# pneumaticsBoard.net
KiCad netlist of a schematic drawn in EAGLE
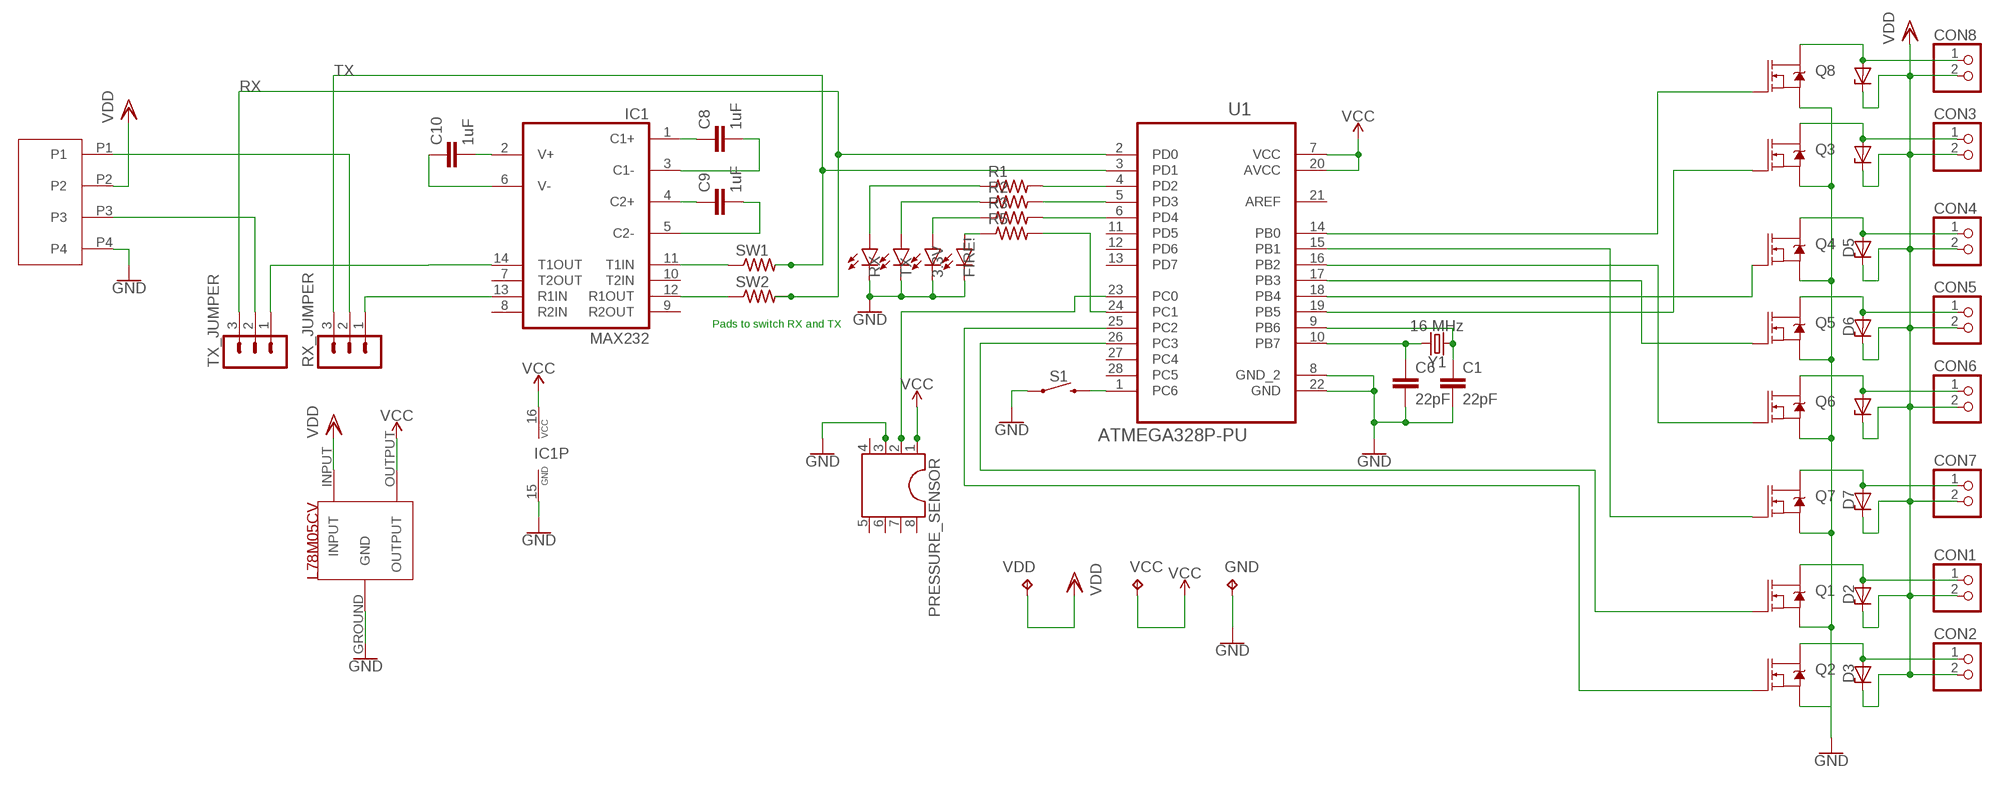
[diagram p0: schematic, sheet 1]

(export (version "E")
  (design (tool "Eeschema 10.0.6"))
  (components
    (comp (ref "3.3V")
      (value "BLUE")
      (footprint "eagle-import:LED-0603")
      (libsource (lib "eagle-import") (part "LED-BLUE0603"))
    )
    (comp (ref "C1")
      (value "22pF")
      (footprint "eagle-import:0603")
      (libsource (lib "eagle-import") (part "470PF-0603-50V-5%"))
    )
    (comp (ref "C6")
      (value "22pF")
      (footprint "eagle-import:0603")
      (libsource (lib "eagle-import") (part "470PF-0603-50V-5%"))
    )
    (comp (ref "C8")
      (value "1uF")
      (footprint "eagle-import:0603")
      (libsource (lib "eagle-import") (part "470PF-0603-50V-5%"))
    )
    (comp (ref "C9")
      (value "1uF")
      (footprint "eagle-import:0603")
      (libsource (lib "eagle-import") (part "470PF-0603-50V-5%"))
    )
    (comp (ref "C10")
      (value "1uF")
      (footprint "eagle-import:0603")
      (libsource (lib "eagle-import") (part "470PF-0603-50V-5%"))
    )
    (comp (ref "CON1")
      (value "PINHD-1X2")
      (footprint "eagle-import:1X02")
      (libsource (lib "eagle-import") (part "PINHD-1X2"))
    )
    (comp (ref "CON2")
      (value "PINHD-1X2")
      (footprint "eagle-import:1X02")
      (libsource (lib "eagle-import") (part "PINHD-1X2"))
    )
    (comp (ref "CON3")
      (value "PINHD-1X2")
      (footprint "eagle-import:1X02")
      (libsource (lib "eagle-import") (part "PINHD-1X2"))
    )
    (comp (ref "CON4")
      (value "PINHD-1X2")
      (footprint "eagle-import:1X02")
      (libsource (lib "eagle-import") (part "PINHD-1X2"))
    )
    (comp (ref "CON5")
      (value "PINHD-1X2")
      (footprint "eagle-import:1X02")
      (libsource (lib "eagle-import") (part "PINHD-1X2"))
    )
    (comp (ref "CON6")
      (value "PINHD-1X2")
      (footprint "eagle-import:1X02")
      (libsource (lib "eagle-import") (part "PINHD-1X2"))
    )
    (comp (ref "CON7")
      (value "PINHD-1X2")
      (footprint "eagle-import:1X02")
      (libsource (lib "eagle-import") (part "PINHD-1X2"))
    )
    (comp (ref "CON8")
      (value "PINHD-1X2")
      (footprint "eagle-import:1X02")
      (libsource (lib "eagle-import") (part "PINHD-1X2"))
    )
    (comp (ref "D1")
      (value "BZX90")
      (footprint "eagle-import:DO34Z7")
      (libsource (lib "eagle-import") (part "BZX90"))
    )
    (comp (ref "D2")
      (value "BZX90")
      (footprint "eagle-import:DO34Z7")
      (libsource (lib "eagle-import") (part "BZX90"))
    )
    (comp (ref "D3")
      (value "BZX90")
      (footprint "eagle-import:DO34Z7")
      (libsource (lib "eagle-import") (part "BZX90"))
    )
    (comp (ref "D4")
      (value "BZX90")
      (footprint "eagle-import:DO34Z7")
      (libsource (lib "eagle-import") (part "BZX90"))
    )
    (comp (ref "D5")
      (value "BZX90")
      (footprint "eagle-import:DO34Z7")
      (libsource (lib "eagle-import") (part "BZX90"))
    )
    (comp (ref "D6")
      (value "BZX90")
      (footprint "eagle-import:DO34Z7")
      (libsource (lib "eagle-import") (part "BZX90"))
    )
    (comp (ref "D7")
      (value "BZX90")
      (footprint "eagle-import:DO34Z7")
      (libsource (lib "eagle-import") (part "BZX90"))
    )
    (comp (ref "D8")
      (value "BZX90")
      (footprint "eagle-import:DO34Z7")
      (libsource (lib "eagle-import") (part "BZX90"))
    )
    (comp (ref "FIRE!")
      (value "BLUE")
      (footprint "eagle-import:LED-0603")
      (libsource (lib "eagle-import") (part "LED-BLUE0603"))
    )
    (comp (ref "GND")
      (value "TPTP11R")
      (footprint "eagle-import:TP11R")
      (libsource (lib "eagle-import") (part "TPTP11R"))
    )
    (comp (ref "IC1")
      (value "MAX232")
      (footprint "eagle-import:DIL16")
      (fields (field (name "MF") "MAXIM") (field (name "MPN") "MAX232ACPE+"))
      (libsource (lib "eagle-import") (part "MAX232"))
    )
    (comp (ref "PRESSURE_SENSOR")
      (value "DIL8")
      (footprint "eagle-import:DIL08")
      (libsource (lib "eagle-import") (part "DIL8"))
    )
    (comp (ref "Q1")
      (value "60V/32A/35mΩ")
      (footprint "eagle-import:TO220V")
      (libsource (lib "eagle-import") (part "MOSFET-NCH-FQP30N06L"))
    )
    (comp (ref "Q2")
      (value "60V/32A/35mΩ")
      (footprint "eagle-import:TO220V")
      (libsource (lib "eagle-import") (part "MOSFET-NCH-FQP30N06L"))
    )
    (comp (ref "Q3")
      (value "60V/32A/35mΩ")
      (footprint "eagle-import:TO220V")
      (libsource (lib "eagle-import") (part "MOSFET-NCH-FQP30N06L"))
    )
    (comp (ref "Q4")
      (value "60V/32A/35mΩ")
      (footprint "eagle-import:TO220V")
      (libsource (lib "eagle-import") (part "MOSFET-NCH-FQP30N06L"))
    )
    (comp (ref "Q5")
      (value "60V/32A/35mΩ")
      (footprint "eagle-import:TO220V")
      (libsource (lib "eagle-import") (part "MOSFET-NCH-FQP30N06L"))
    )
    (comp (ref "Q6")
      (value "60V/32A/35mΩ")
      (footprint "eagle-import:TO220V")
      (libsource (lib "eagle-import") (part "MOSFET-NCH-FQP30N06L"))
    )
    (comp (ref "Q7")
      (value "60V/32A/35mΩ")
      (footprint "eagle-import:TO220V")
      (libsource (lib "eagle-import") (part "MOSFET-NCH-FQP30N06L"))
    )
    (comp (ref "Q8")
      (value "60V/32A/35mΩ")
      (footprint "eagle-import:TO220V")
      (libsource (lib "eagle-import") (part "MOSFET-NCH-FQP30N06L"))
    )
    (comp (ref "R1")
      (value "R-US_0204/2V")
      (footprint "eagle-import:0204V")
      (libsource (lib "eagle-import") (part "R-US_0204/2V"))
    )
    (comp (ref "R2")
      (value "R-US_0204/2V")
      (footprint "eagle-import:0204V")
      (libsource (lib "eagle-import") (part "R-US_0204/2V"))
    )
    (comp (ref "R3")
      (value "R-US_0204/2V")
      (footprint "eagle-import:0204V")
      (libsource (lib "eagle-import") (part "R-US_0204/2V"))
    )
    (comp (ref "R5")
      (value "R-US_0204/2V")
      (footprint "eagle-import:0204V")
      (libsource (lib "eagle-import") (part "R-US_0204/2V"))
    )
    (comp (ref "RX")
      (value "BLUE")
      (footprint "eagle-import:LED-0603")
      (libsource (lib "eagle-import") (part "LED-BLUE0603"))
    )
    (comp (ref "RX_JUMPER")
      (value "MA03-1")
      (footprint "eagle-import:MA03-1")
      (libsource (lib "eagle-import") (part "MA03-1"))
    )
    (comp (ref "S1")
      (value "MOMENTARY-SWITCH-SPST-PTH-6.0MM")
      (footprint "eagle-import:TACTILE_SWITCH_PTH_6.0MM")
      (libsource (lib "eagle-import") (part "MOMENTARY-SWITCH-SPST-PTH-6.0MM"))
    )
    (comp (ref "SW1")
      (value "R-US_0204/2V")
      (footprint "eagle-import:0204V")
      (libsource (lib "eagle-import") (part "R-US_0204/2V"))
    )
    (comp (ref "SW2")
      (value "R-US_0204/2V")
      (footprint "eagle-import:0204V")
      (libsource (lib "eagle-import") (part "R-US_0204/2V"))
    )
    (comp (ref "TX")
      (value "BLUE")
      (footprint "eagle-import:LED-0603")
      (libsource (lib "eagle-import") (part "LED-BLUE0603"))
    )
    (comp (ref "TX_JUMPER")
      (value "MA03-1")
      (footprint "eagle-import:MA03-1")
      (libsource (lib "eagle-import") (part "MA03-1"))
    )
    (comp (ref "U$1")
      (value "L78M05CV")
      (footprint "eagle-import:L78M05CV")
      (libsource (lib "eagle-import") (part "L78M05CV"))
    )
    (comp (ref "U$2")
      (value "MINI_FIT_JR_4PIN_VERT")
      (footprint "eagle-import:MINI_FIT_JR_4PIN_VERT")
      (libsource (lib "eagle-import") (part "MINI_FIT_JR_4PIN_VERT"))
    )
    (comp (ref "U1")
      (value "ATMEGA328P-PU")
      (footprint "eagle-import:DIP254P762X457-28")
      (libsource (lib "eagle-import") (part "ATMEGA328P-PU"))
    )
    (comp (ref "VCC")
      (value "TPTP11R")
      (footprint "eagle-import:TP11R")
      (libsource (lib "eagle-import") (part "TPTP11R"))
    )
    (comp (ref "VDD")
      (value "TPTP11R")
      (footprint "eagle-import:TP11R")
      (libsource (lib "eagle-import") (part "TPTP11R"))
    )
    (comp (ref "Y1")
      (value "16 MHz")
      (footprint "eagle-import:HC49U")
      (libsource (lib "eagle-import") (part "CRYSTALPTH-HC49UV"))
    )
  )
  (nets
    (net (code "1") (name "/RX") (class "Default")
      (node (ref "SW2") (pin "2") (pinfunction "2_2") (pintype "passive"))
      (node (ref "TX_JUMPER") (pin "3") (pinfunction "3_3") (pintype "passive"))
      (node (ref "U1") (pin "2") (pinfunction "PD0_2") (pintype "bidirectional"))
    )
    (net (code "2") (name "/TX") (class "Default")
      (node (ref "RX_JUMPER") (pin "3") (pinfunction "3_3") (pintype "passive"))
      (node (ref "SW1") (pin "2") (pinfunction "2_2") (pintype "passive"))
      (node (ref "U1") (pin "3") (pinfunction "PD1_3") (pintype "bidirectional"))
    )
    (net (code "3") (name "GND") (class "Default")
      (node (ref "3.3V") (pin "C") (pinfunction "C_C") (pintype "passive"))
      (node (ref "C1") (pin "2") (pinfunction "2_2") (pintype "passive"))
      (node (ref "C6") (pin "2") (pinfunction "2_2") (pintype "passive"))
      (node (ref "FIRE!") (pin "C") (pinfunction "C_C") (pintype "passive"))
      (node (ref "GND") (pin "TP") (pinfunction "TP_TP") (pintype "input"))
      (node (ref "IC1") (pin "15") (pinfunction "GND_15") (pintype "power_in"))
      (node (ref "PRESSURE_SENSOR") (pin "3") (pinfunction "3_3") (pintype "passive"))
      (node (ref "Q1") (pin "3") (pinfunction "S_3") (pintype "bidirectional"))
      (node (ref "Q2") (pin "3") (pinfunction "S_3") (pintype "bidirectional"))
      (node (ref "Q3") (pin "3") (pinfunction "S_3") (pintype "bidirectional"))
      (node (ref "Q4") (pin "3") (pinfunction "S_3") (pintype "bidirectional"))
      (node (ref "Q5") (pin "3") (pinfunction "S_3") (pintype "bidirectional"))
      (node (ref "Q6") (pin "3") (pinfunction "S_3") (pintype "bidirectional"))
      (node (ref "Q7") (pin "3") (pinfunction "S_3") (pintype "bidirectional"))
      (node (ref "Q8") (pin "3") (pinfunction "S_3") (pintype "bidirectional"))
      (node (ref "RX") (pin "C") (pinfunction "C_C") (pintype "passive"))
      (node (ref "S1") (pin "1") (pinfunction "1_1") (pintype "passive"))
      (node (ref "TX") (pin "C") (pinfunction "C_C") (pintype "passive"))
      (node (ref "U$1") (pin "GROUND") (pinfunction "GND_GROUND") (pintype "bidirectional"))
      (node (ref "U$2") (pin "P4") (pinfunction "P4_P4") (pintype "bidirectional"))
      (node (ref "U1") (pin "22") (pinfunction "GND_22") (pintype "passive"))
      (node (ref "U1") (pin "8") (pinfunction "GND_2_8") (pintype "passive"))
    )
    (net (code "4") (name "Net-(3.3V-PadA)") (class "Default")
      (node (ref "3.3V") (pin "A") (pinfunction "A_A") (pintype "passive"))
      (node (ref "R3") (pin "1") (pinfunction "1_1") (pintype "passive"))
    )
    (net (code "5") (name "Net-(FIRE!-PadA)") (class "Default")
      (node (ref "FIRE!") (pin "A") (pinfunction "A_A") (pintype "passive"))
      (node (ref "R5") (pin "1") (pinfunction "1_1") (pintype "passive"))
    )
    (net (code "6") (name "Net-(IC1A-C1+)") (class "Default")
      (node (ref "C8") (pin "1") (pinfunction "1_1") (pintype "passive"))
      (node (ref "IC1") (pin "1") (pinfunction "C1+_1") (pintype "bidirectional"))
    )
    (net (code "7") (name "Net-(IC1A-C1-)") (class "Default")
      (node (ref "C8") (pin "2") (pinfunction "2_2") (pintype "passive"))
      (node (ref "IC1") (pin "3") (pinfunction "C1-_3") (pintype "bidirectional"))
    )
    (net (code "8") (name "Net-(IC1A-C2+)") (class "Default")
      (node (ref "C9") (pin "1") (pinfunction "1_1") (pintype "passive"))
      (node (ref "IC1") (pin "4") (pinfunction "C2+_4") (pintype "bidirectional"))
    )
    (net (code "9") (name "Net-(IC1A-C2-)") (class "Default")
      (node (ref "C9") (pin "2") (pinfunction "2_2") (pintype "passive"))
      (node (ref "IC1") (pin "5") (pinfunction "C2-_5") (pintype "bidirectional"))
    )
    (net (code "10") (name "Net-(IC1A-R1IN)") (class "Default")
      (node (ref "IC1") (pin "13") (pinfunction "R1IN_13") (pintype "input"))
      (node (ref "RX_JUMPER") (pin "1") (pinfunction "1_1") (pintype "passive"))
    )
    (net (code "11") (name "Net-(IC1A-R1OUT)") (class "Default")
      (node (ref "IC1") (pin "12") (pinfunction "R1OUT_12") (pintype "output"))
      (node (ref "SW2") (pin "1") (pinfunction "1_1") (pintype "passive"))
    )
    (net (code "12") (name "Net-(IC1A-T1IN)") (class "Default")
      (node (ref "IC1") (pin "11") (pinfunction "T1IN_11") (pintype "input"))
      (node (ref "SW1") (pin "1") (pinfunction "1_1") (pintype "passive"))
    )
    (net (code "13") (name "Net-(IC1A-T1OUT)") (class "Default")
      (node (ref "IC1") (pin "14") (pinfunction "T1OUT_14") (pintype "output"))
      (node (ref "TX_JUMPER") (pin "1") (pinfunction "1_1") (pintype "passive"))
    )
    (net (code "14") (name "Net-(IC1A-V+)") (class "Default")
      (node (ref "C10") (pin "2") (pinfunction "2_2") (pintype "passive"))
      (node (ref "IC1") (pin "2") (pinfunction "V+_2") (pintype "bidirectional"))
    )
    (net (code "15") (name "Net-(IC1A-V-)") (class "Default")
      (node (ref "C10") (pin "1") (pinfunction "1_1") (pintype "passive"))
      (node (ref "IC1") (pin "6") (pinfunction "V-_6") (pintype "bidirectional"))
    )
    (net (code "16") (name "Net-(Q1-D)") (class "Default")
      (node (ref "CON1") (pin "1") (pinfunction "1_1") (pintype "passive"))
      (node (ref "D2") (pin "A") (pinfunction "A_A") (pintype "passive"))
      (node (ref "Q1") (pin "2") (pinfunction "D_2") (pintype "bidirectional"))
    )
    (net (code "17") (name "Net-(Q1-G)") (class "Default")
      (node (ref "Q1") (pin "1") (pinfunction "G_1") (pintype "bidirectional"))
      (node (ref "U1") (pin "26") (pinfunction "PC3_26") (pintype "bidirectional"))
    )
    (net (code "18") (name "Net-(Q2-D)") (class "Default")
      (node (ref "CON2") (pin "1") (pinfunction "1_1") (pintype "passive"))
      (node (ref "D3") (pin "A") (pinfunction "A_A") (pintype "passive"))
      (node (ref "Q2") (pin "2") (pinfunction "D_2") (pintype "bidirectional"))
    )
    (net (code "19") (name "Net-(Q2-G)") (class "Default")
      (node (ref "Q2") (pin "1") (pinfunction "G_1") (pintype "bidirectional"))
      (node (ref "U1") (pin "25") (pinfunction "PC2_25") (pintype "bidirectional"))
    )
    (net (code "20") (name "Net-(Q3-D)") (class "Default")
      (node (ref "CON3") (pin "1") (pinfunction "1_1") (pintype "passive"))
      (node (ref "D4") (pin "A") (pinfunction "A_A") (pintype "passive"))
      (node (ref "Q3") (pin "2") (pinfunction "D_2") (pintype "bidirectional"))
    )
    (net (code "21") (name "Net-(Q3-G)") (class "Default")
      (node (ref "Q3") (pin "1") (pinfunction "G_1") (pintype "bidirectional"))
      (node (ref "U1") (pin "19") (pinfunction "PB5_19") (pintype "bidirectional"))
    )
    (net (code "22") (name "Net-(Q4-D)") (class "Default")
      (node (ref "CON4") (pin "1") (pinfunction "1_1") (pintype "passive"))
      (node (ref "D5") (pin "A") (pinfunction "A_A") (pintype "passive"))
      (node (ref "Q4") (pin "2") (pinfunction "D_2") (pintype "bidirectional"))
    )
    (net (code "23") (name "Net-(Q4-G)") (class "Default")
      (node (ref "Q4") (pin "1") (pinfunction "G_1") (pintype "bidirectional"))
      (node (ref "U1") (pin "18") (pinfunction "PB4_18") (pintype "bidirectional"))
    )
    (net (code "24") (name "Net-(Q5-D)") (class "Default")
      (node (ref "CON5") (pin "1") (pinfunction "1_1") (pintype "passive"))
      (node (ref "D6") (pin "A") (pinfunction "A_A") (pintype "passive"))
      (node (ref "Q5") (pin "2") (pinfunction "D_2") (pintype "bidirectional"))
    )
    (net (code "25") (name "Net-(Q5-G)") (class "Default")
      (node (ref "Q5") (pin "1") (pinfunction "G_1") (pintype "bidirectional"))
      (node (ref "U1") (pin "17") (pinfunction "PB3_17") (pintype "bidirectional"))
    )
    (net (code "26") (name "Net-(Q6-D)") (class "Default")
      (node (ref "CON6") (pin "1") (pinfunction "1_1") (pintype "passive"))
      (node (ref "D8") (pin "A") (pinfunction "A_A") (pintype "passive"))
      (node (ref "Q6") (pin "2") (pinfunction "D_2") (pintype "bidirectional"))
    )
    (net (code "27") (name "Net-(Q6-G)") (class "Default")
      (node (ref "Q6") (pin "1") (pinfunction "G_1") (pintype "bidirectional"))
      (node (ref "U1") (pin "16") (pinfunction "PB2_16") (pintype "bidirectional"))
    )
    (net (code "28") (name "Net-(Q7-D)") (class "Default")
      (node (ref "CON7") (pin "1") (pinfunction "1_1") (pintype "passive"))
      (node (ref "D7") (pin "A") (pinfunction "A_A") (pintype "passive"))
      (node (ref "Q7") (pin "2") (pinfunction "D_2") (pintype "bidirectional"))
    )
    (net (code "29") (name "Net-(Q7-G)") (class "Default")
      (node (ref "Q7") (pin "1") (pinfunction "G_1") (pintype "bidirectional"))
      (node (ref "U1") (pin "15") (pinfunction "PB1_15") (pintype "bidirectional"))
    )
    (net (code "30") (name "Net-(Q8-D)") (class "Default")
      (node (ref "CON8") (pin "1") (pinfunction "1_1") (pintype "passive"))
      (node (ref "D1") (pin "A") (pinfunction "A_A") (pintype "passive"))
      (node (ref "Q8") (pin "2") (pinfunction "D_2") (pintype "bidirectional"))
    )
    (net (code "31") (name "Net-(Q8-G)") (class "Default")
      (node (ref "Q8") (pin "1") (pinfunction "G_1") (pintype "bidirectional"))
      (node (ref "U1") (pin "14") (pinfunction "PB0_14") (pintype "bidirectional"))
    )
    (net (code "32") (name "Net-(R1-Pad1)") (class "Default")
      (node (ref "R1") (pin "1") (pinfunction "1_1") (pintype "passive"))
      (node (ref "RX") (pin "A") (pinfunction "A_A") (pintype "passive"))
    )
    (net (code "33") (name "Net-(R2-Pad1)") (class "Default")
      (node (ref "R2") (pin "1") (pinfunction "1_1") (pintype "passive"))
      (node (ref "TX") (pin "A") (pinfunction "A_A") (pintype "passive"))
    )
    (net (code "34") (name "Net-(RX_JUMPER-Pad2)") (class "Default")
      (node (ref "RX_JUMPER") (pin "2") (pinfunction "2_2") (pintype "passive"))
      (node (ref "U$2") (pin "P1") (pinfunction "P1_P1") (pintype "bidirectional"))
    )
    (net (code "35") (name "Net-(S1-2)") (class "Default")
      (node (ref "S1") (pin "3") (pinfunction "2_3") (pintype "passive"))
      (node (ref "U1") (pin "1") (pinfunction "PC6_1") (pintype "bidirectional"))
    )
    (net (code "36") (name "Net-(TX_JUMPER-Pad2)") (class "Default")
      (node (ref "TX_JUMPER") (pin "2") (pinfunction "2_2") (pintype "passive"))
      (node (ref "U$2") (pin "P3") (pinfunction "P3_P3") (pintype "bidirectional"))
    )
    (net (code "37") (name "Net-(U1-PB6)") (class "Default")
      (node (ref "C1") (pin "1") (pinfunction "1_1") (pintype "passive"))
      (node (ref "U1") (pin "9") (pinfunction "PB6_9") (pintype "bidirectional"))
      (node (ref "Y1") (pin "1") (pinfunction "1_1") (pintype "passive"))
    )
    (net (code "38") (name "Net-(U1-PB7)") (class "Default")
      (node (ref "C6") (pin "1") (pinfunction "1_1") (pintype "passive"))
      (node (ref "U1") (pin "10") (pinfunction "PB7_10") (pintype "bidirectional"))
      (node (ref "Y1") (pin "2") (pinfunction "2_2") (pintype "passive"))
    )
    (net (code "39") (name "Net-(U1-PC0)") (class "Default")
      (node (ref "PRESSURE_SENSOR") (pin "2") (pinfunction "2_2") (pintype "passive"))
      (node (ref "U1") (pin "23") (pinfunction "PC0_23") (pintype "bidirectional"))
    )
    (net (code "40") (name "Net-(U1-PC1)") (class "Default")
      (node (ref "R5") (pin "2") (pinfunction "2_2") (pintype "passive"))
      (node (ref "U1") (pin "24") (pinfunction "PC1_24") (pintype "bidirectional"))
    )
    (net (code "41") (name "Net-(U1-PD2)") (class "Default")
      (node (ref "R1") (pin "2") (pinfunction "2_2") (pintype "passive"))
      (node (ref "U1") (pin "4") (pinfunction "PD2_4") (pintype "bidirectional"))
    )
    (net (code "42") (name "Net-(U1-PD3)") (class "Default")
      (node (ref "R2") (pin "2") (pinfunction "2_2") (pintype "passive"))
      (node (ref "U1") (pin "5") (pinfunction "PD3_5") (pintype "bidirectional"))
    )
    (net (code "43") (name "Net-(U1-PD4)") (class "Default")
      (node (ref "R3") (pin "2") (pinfunction "2_2") (pintype "passive"))
      (node (ref "U1") (pin "6") (pinfunction "PD4_6") (pintype "bidirectional"))
    )
    (net (code "44") (name "VCC") (class "Default")
      (node (ref "IC1") (pin "16") (pinfunction "VCC_16") (pintype "power_in"))
      (node (ref "PRESSURE_SENSOR") (pin "1") (pinfunction "1_1") (pintype "passive"))
      (node (ref "U$1") (pin "OUTPUT") (pinfunction "OUTPUT_OUTPUT") (pintype "bidirectional"))
      (node (ref "U1") (pin "20") (pinfunction "AVCC_20") (pintype "power_in"))
      (node (ref "U1") (pin "7") (pinfunction "VCC_7") (pintype "power_in"))
      (node (ref "VCC") (pin "TP") (pinfunction "TP_TP") (pintype "input"))
    )
    (net (code "45") (name "VDD") (class "Default")
      (node (ref "CON1") (pin "2") (pinfunction "2_2") (pintype "passive"))
      (node (ref "CON2") (pin "2") (pinfunction "2_2") (pintype "passive"))
      (node (ref "CON3") (pin "2") (pinfunction "2_2") (pintype "passive"))
      (node (ref "CON4") (pin "2") (pinfunction "2_2") (pintype "passive"))
      (node (ref "CON5") (pin "2") (pinfunction "2_2") (pintype "passive"))
      (node (ref "CON6") (pin "2") (pinfunction "2_2") (pintype "passive"))
      (node (ref "CON7") (pin "2") (pinfunction "2_2") (pintype "passive"))
      (node (ref "CON8") (pin "2") (pinfunction "2_2") (pintype "passive"))
      (node (ref "D1") (pin "C") (pinfunction "C_C") (pintype "passive"))
      (node (ref "D2") (pin "C") (pinfunction "C_C") (pintype "passive"))
      (node (ref "D3") (pin "C") (pinfunction "C_C") (pintype "passive"))
      (node (ref "D4") (pin "C") (pinfunction "C_C") (pintype "passive"))
      (node (ref "D5") (pin "C") (pinfunction "C_C") (pintype "passive"))
      (node (ref "D6") (pin "C") (pinfunction "C_C") (pintype "passive"))
      (node (ref "D7") (pin "C") (pinfunction "C_C") (pintype "passive"))
      (node (ref "D8") (pin "C") (pinfunction "C_C") (pintype "passive"))
      (node (ref "U$1") (pin "INPUT") (pinfunction "INPUT_INPUT") (pintype "bidirectional"))
      (node (ref "U$2") (pin "P2") (pinfunction "P2_P2") (pintype "bidirectional"))
      (node (ref "VDD") (pin "TP") (pinfunction "TP_TP") (pintype "input"))
    )
    (net (code "46") (name "unconnected-(IC1A-R2IN-Pad8)") (class "Default")
      (node (ref "IC1") (pin "8") (pinfunction "R2IN_8") (pintype "input"))
    )
    (net (code "47") (name "unconnected-(IC1A-R2OUT-Pad9)") (class "Default")
      (node (ref "IC1") (pin "9") (pinfunction "R2OUT_9") (pintype "output"))
    )
    (net (code "48") (name "unconnected-(IC1A-T2IN-Pad10)") (class "Default")
      (node (ref "IC1") (pin "10") (pinfunction "T2IN_10") (pintype "input"))
    )
    (net (code "49") (name "unconnected-(IC1A-T2OUT-Pad7)") (class "Default")
      (node (ref "IC1") (pin "7") (pinfunction "T2OUT_7") (pintype "output"))
    )
    (net (code "50") (name "unconnected-(PRESSURE_SENSOR-Pad4)") (class "Default")
      (node (ref "PRESSURE_SENSOR") (pin "4") (pinfunction "4_4") (pintype "passive"))
    )
    (net (code "51") (name "unconnected-(PRESSURE_SENSOR-Pad5)") (class "Default")
      (node (ref "PRESSURE_SENSOR") (pin "5") (pinfunction "5_5") (pintype "passive"))
    )
    (net (code "52") (name "unconnected-(PRESSURE_SENSOR-Pad6)") (class "Default")
      (node (ref "PRESSURE_SENSOR") (pin "6") (pinfunction "6_6") (pintype "passive"))
    )
    (net (code "53") (name "unconnected-(PRESSURE_SENSOR-Pad7)") (class "Default")
      (node (ref "PRESSURE_SENSOR") (pin "7") (pinfunction "7_7") (pintype "passive"))
    )
    (net (code "54") (name "unconnected-(PRESSURE_SENSOR-Pad8)") (class "Default")
      (node (ref "PRESSURE_SENSOR") (pin "8") (pinfunction "8_8") (pintype "passive"))
    )
    (net (code "55") (name "unconnected-(U1-AREF-Pad21)") (class "Default")
      (node (ref "U1") (pin "21") (pinfunction "AREF_21") (pintype "input"))
    )
    (net (code "56") (name "unconnected-(U1-PC4-Pad27)") (class "Default")
      (node (ref "U1") (pin "27") (pinfunction "PC4_27") (pintype "bidirectional"))
    )
    (net (code "57") (name "unconnected-(U1-PC5-Pad28)") (class "Default")
      (node (ref "U1") (pin "28") (pinfunction "PC5_28") (pintype "bidirectional"))
    )
    (net (code "58") (name "unconnected-(U1-PD5-Pad11)") (class "Default")
      (node (ref "U1") (pin "11") (pinfunction "PD5_11") (pintype "bidirectional"))
    )
    (net (code "59") (name "unconnected-(U1-PD6-Pad12)") (class "Default")
      (node (ref "U1") (pin "12") (pinfunction "PD6_12") (pintype "bidirectional"))
    )
    (net (code "60") (name "unconnected-(U1-PD7-Pad13)") (class "Default")
      (node (ref "U1") (pin "13") (pinfunction "PD7_13") (pintype "bidirectional"))
    )
  )
)
